# BMS_V1.net
KiCad netlist of a schematic drawn in Altium Designer
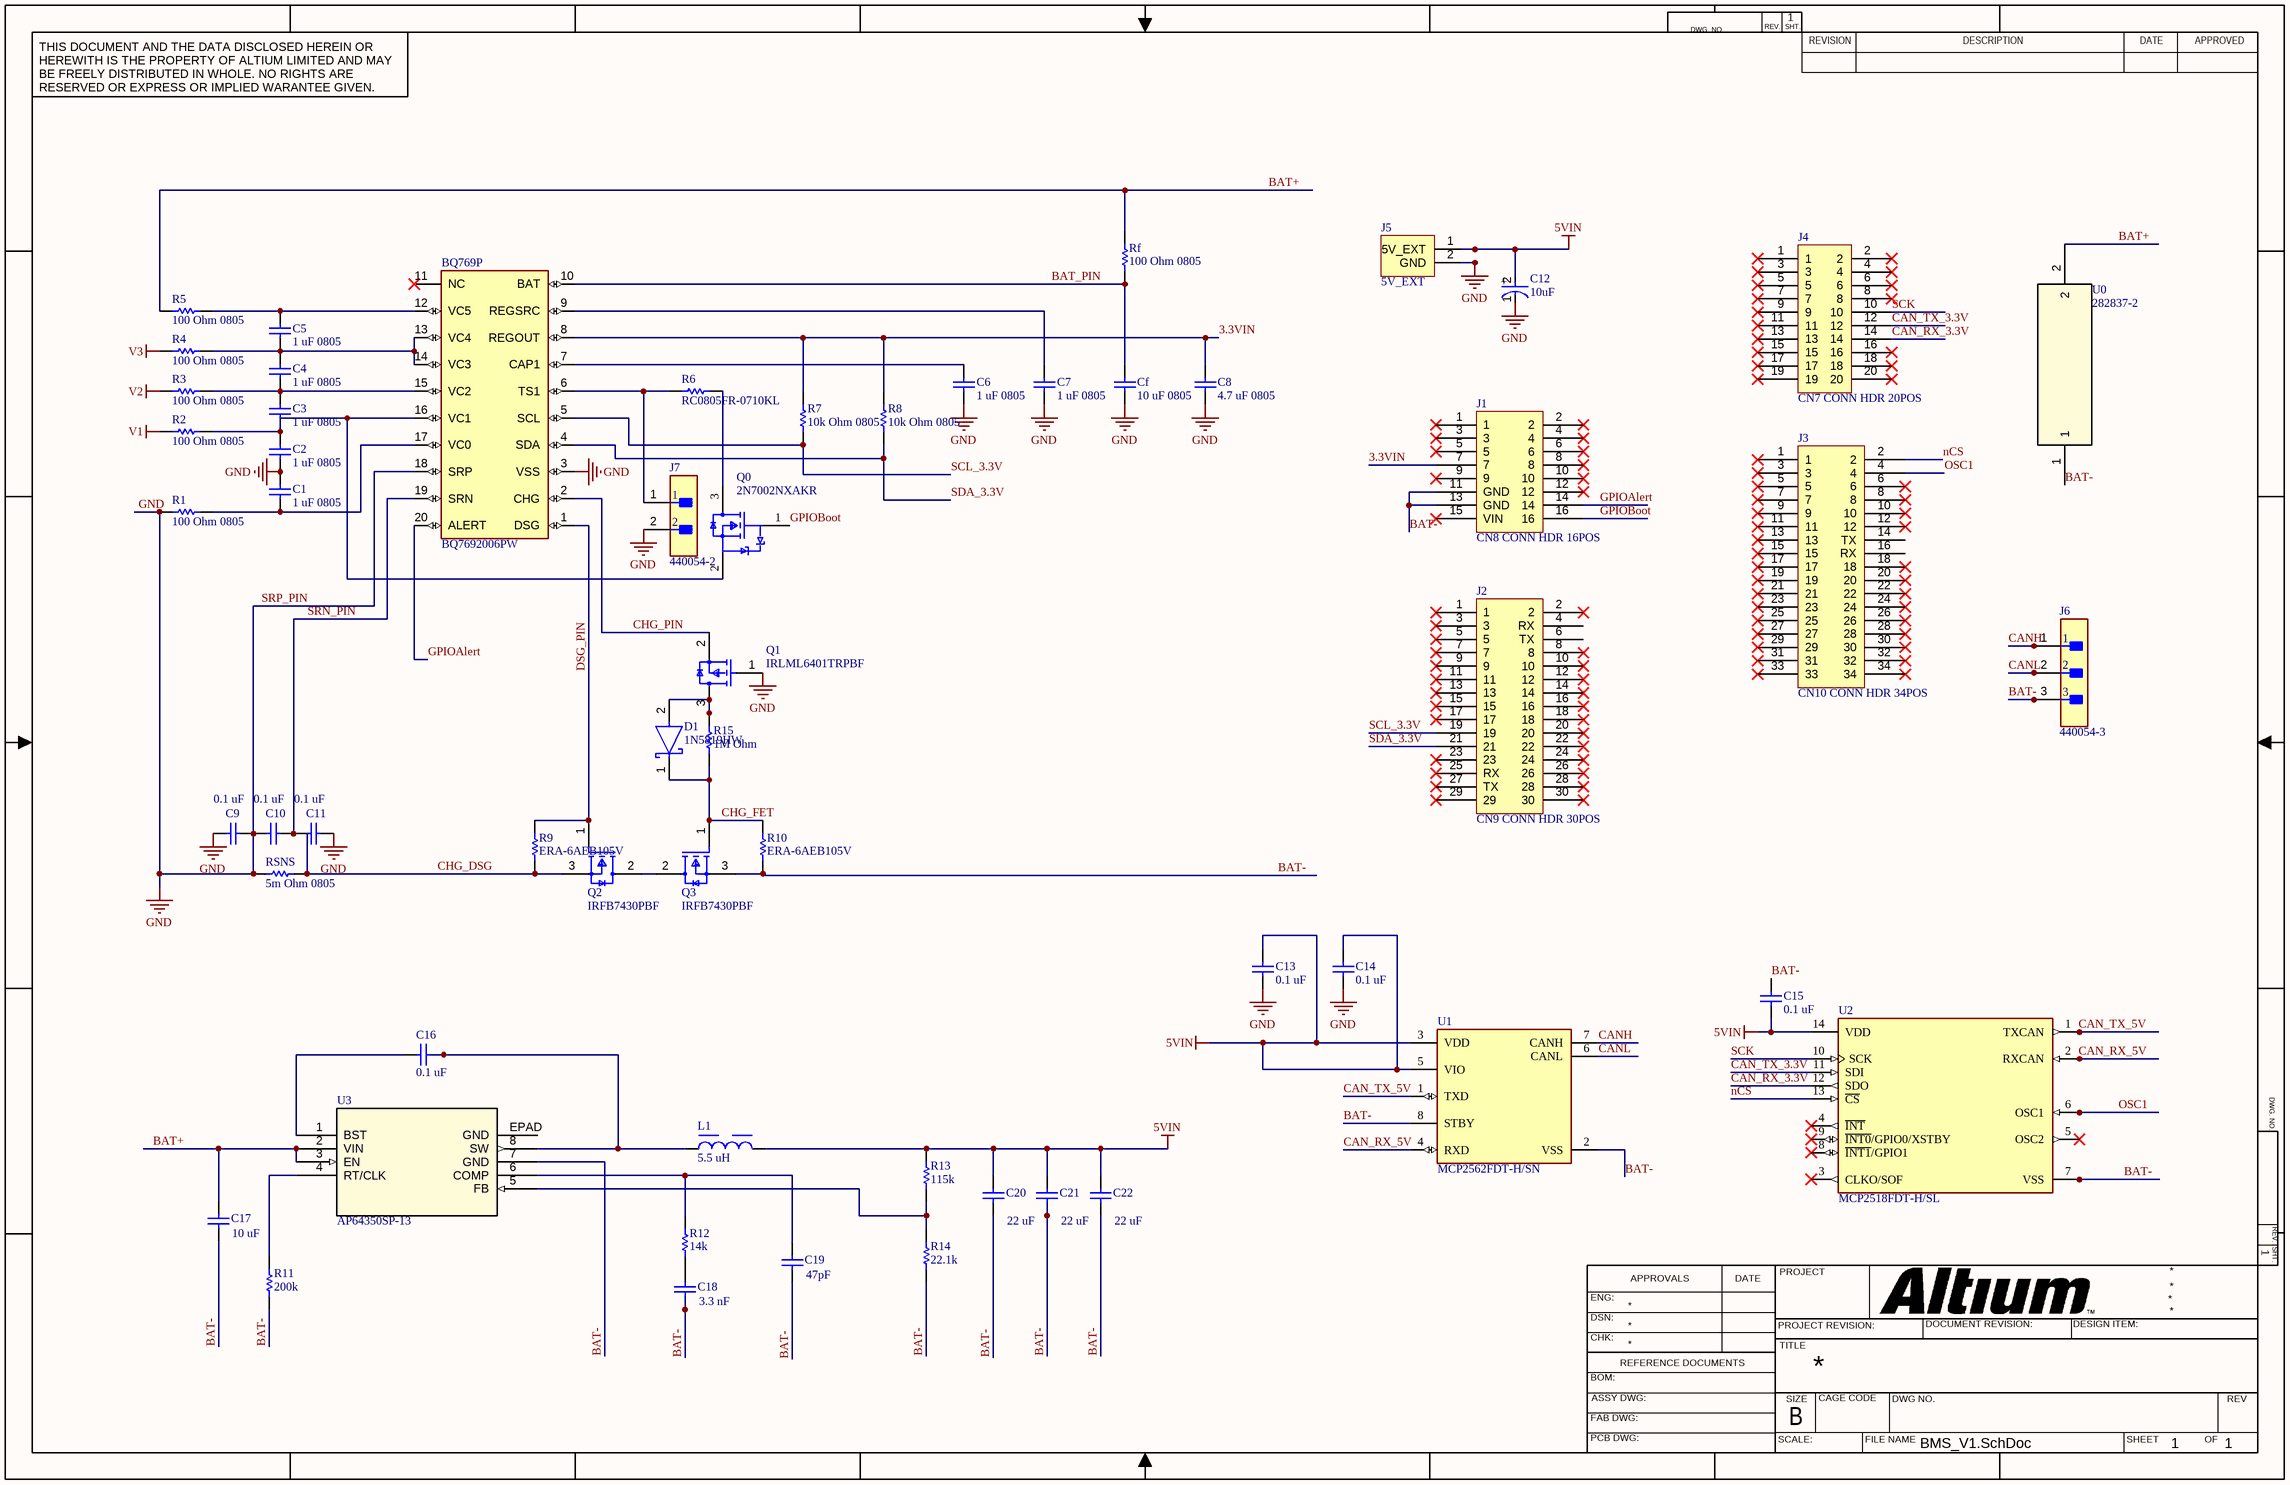
[diagram p0: BMS_V1.SchDoc]

(export (version "E")
  (design (tool "Eeschema 10.0.6"))
  (components
    (comp (ref "BQ769P")
      (value "BQ7692006PW")
      (footprint "BQ7692006PW")
      (description "3 to 5-Series Cell Li-Ion and Li-Phosphate Battery Monitor (bq76940 Family)")
      (fields (field (name "MF") "Texas Instruments"))
      (libsource (lib "Mars Colony") (part "BQ7692006PW"))
    )
    (comp (ref "C1")
      (value "1 uF 0805")
      (footprint "CAPC2013X140X50LL20T25")
      (fields (field (name "PART NUMBER") "C0805C105K3RACTU") (field (name "MANUFACTURER") "Kemet"))
      (libsource (lib "Altium Content Vault") (part "CAP"))
    )
    (comp (ref "C2")
      (value "1 uF 0805")
      (footprint "CAPC2013X140X50LL20T25")
      (fields (field (name "PART NUMBER") "C0805C105K3RACTU") (field (name "MANUFACTURER") "Kemet"))
      (libsource (lib "Altium Content Vault") (part "CAP"))
    )
    (comp (ref "C3")
      (value "1 uF 0805")
      (footprint "CAPC2013X140X50LL20T25")
      (fields (field (name "PART NUMBER") "C0805C105K3RACTU") (field (name "MANUFACTURER") "Kemet"))
      (libsource (lib "Altium Content Vault") (part "CAP"))
    )
    (comp (ref "C4")
      (value "1 uF 0805")
      (footprint "CAPC2013X140X50LL20T25")
      (fields (field (name "PART NUMBER") "C0805C105K3RACTU") (field (name "MANUFACTURER") "Kemet"))
      (libsource (lib "Altium Content Vault") (part "CAP"))
    )
    (comp (ref "C5")
      (value "1 uF 0805")
      (footprint "CAPC2013X140X50LL20T25")
      (fields (field (name "PART NUMBER") "C0805C105K3RACTU") (field (name "MANUFACTURER") "Kemet"))
      (libsource (lib "Altium Content Vault") (part "CAP"))
    )
    (comp (ref "C6")
      (value "1 uF 0805")
      (footprint "CAPC2013X140X50LL20T25")
      (fields (field (name "PART NUMBER") "C0805C105K3RACTU") (field (name "MANUFACTURER") "Kemet"))
      (libsource (lib "Altium Content Vault") (part "CAP"))
    )
    (comp (ref "C7")
      (value "1 uF 0805")
      (footprint "CAPC2013X140X50LL20T25")
      (fields (field (name "PART NUMBER") "C0805C105K3RACTU") (field (name "MANUFACTURER") "Kemet"))
      (libsource (lib "Altium Content Vault") (part "CAP"))
    )
    (comp (ref "C8")
      (value "4.7 uF 0805")
      (footprint "CAPC2013X140X50LL20T25")
      (fields (field (name "PART NUMBER") "C0805C105K3RACTU") (field (name "MANUFACTURER") "Kemet"))
      (libsource (lib "Altium Content Vault") (part "CAP"))
    )
    (comp (ref "C9")
      (value "0.1 uF")
      (footprint "CAPC2013X140X50LL20T25")
      (fields (field (name "PART NUMBER") "C0805C105K3RACTU") (field (name "MANUFACTURER") "Kemet"))
      (libsource (lib "Altium Content Vault") (part "CAP"))
    )
    (comp (ref "C10")
      (value "0.1 uF")
      (footprint "CAPC2013X140X50LL20T25")
      (fields (field (name "PART NUMBER") "C0805C105K3RACTU") (field (name "MANUFACTURER") "Kemet"))
      (libsource (lib "Altium Content Vault") (part "CAP"))
    )
    (comp (ref "C11")
      (value "0.1 uF")
      (footprint "CAPC2013X140X50LL20T25")
      (fields (field (name "PART NUMBER") "C0805C105K3RACTU") (field (name "MANUFACTURER") "Kemet"))
      (libsource (lib "Altium Content Vault") (part "CAP"))
    )
    (comp (ref "C12")
      (value "10uF")
      (footprint "FP-FKC-MFG")
      (description "CAP ALUM 10UF 20% 50V SMD")
      (fields (field (name "TOLERANCE") "20%") (field (name "VOLTAGE") "50V"))
      (libsource (lib "Altium Content Vault") (part "a00bbbee19879c290e62620ae7e47b1"))
    )
    (comp (ref "C13")
      (value "0.1 uF")
      (footprint "CAPC2013X135X45NL10T25")
      (description "Chip Capacitor, 4.7 uF, +/- 10%, 16 V, -55 to 85 degC, 0805 (2012 Metric), RoHS, Tape and Reel")
      (fields (field (name "TOLERANCE") "10%") (field (name "PARTNUMBER") "GRM21BR61C475KA88L"))
      (libsource (lib "Altium Content Vault") (part "CAP-NP-2"))
    )
    (comp (ref "C14")
      (value "0.1 uF")
      (footprint "CAPC2013X135X45NL10T25")
      (description "Chip Capacitor, 4.7 uF, +/- 10%, 16 V, -55 to 85 degC, 0805 (2012 Metric), RoHS, Tape and Reel")
      (fields (field (name "TOLERANCE") "10%") (field (name "PARTNUMBER") "GRM21BR61C475KA88L"))
      (libsource (lib "Altium Content Vault") (part "CAP-NP-2"))
    )
    (comp (ref "C15")
      (value "0.1 uF")
      (footprint "CAPC2013X135X45NL10T25")
      (description "Chip Capacitor, 4.7 uF, +/- 10%, 16 V, -55 to 85 degC, 0805 (2012 Metric), RoHS, Tape and Reel")
      (fields (field (name "TOLERANCE") "10%") (field (name "PARTNUMBER") "GRM21BR61C475KA88L"))
      (libsource (lib "Altium Content Vault") (part "CAP-NP-2"))
    )
    (comp (ref "C16")
      (value "0.1 uF")
      (footprint "CAPC2013X135X45NL10T25")
      (description "Chip Capacitor, 4.7 uF, +/- 10%, 16 V, -55 to 85 degC, 0805 (2012 Metric), RoHS, Tape and Reel")
      (fields (field (name "TOLERANCE") "10%") (field (name "PARTNUMBER") "GRM21BR61C475KA88L"))
      (libsource (lib "Altium Content Vault") (part "CAP-NP-2"))
    )
    (comp (ref "C17")
      (value "10 uF")
      (footprint "CAPC2013X135X45NL10T25")
      (description "Chip Capacitor, 4.7 uF, +/- 10%, 16 V, -55 to 85 degC, 0805 (2012 Metric), RoHS, Tape and Reel")
      (fields (field (name "TOLERANCE") "10%") (field (name "PARTNUMBER") "GRM21BR61C475KA88L"))
      (libsource (lib "Altium Content Vault") (part "CAP-NP-2"))
    )
    (comp (ref "C18")
      (value "3.3 nF")
      (footprint "CAPC2013X135X45NL10T25")
      (description "Chip Capacitor, 4.7 uF, +/- 10%, 16 V, -55 to 85 degC, 0805 (2012 Metric), RoHS, Tape and Reel")
      (fields (field (name "TOLERANCE") "10%") (field (name "PARTNUMBER") "GRM21BR61C475KA88L"))
      (libsource (lib "Altium Content Vault") (part "CAP-NP-2"))
    )
    (comp (ref "C19")
      (value "47pF")
      (footprint "CAPC2013X135X45NL10T25")
      (description "Chip Capacitor, 4.7 uF, +/- 10%, 16 V, -55 to 85 degC, 0805 (2012 Metric), RoHS, Tape and Reel")
      (fields (field (name "TOLERANCE") "10%") (field (name "PARTNUMBER") "GRM21BR61C475KA88L"))
      (libsource (lib "Altium Content Vault") (part "CAP-NP-2"))
    )
    (comp (ref "C20")
      (value "22 uF")
      (footprint "CAPC2013X135X45NL10T25")
      (description "Chip Capacitor, 4.7 uF, +/- 10%, 16 V, -55 to 85 degC, 0805 (2012 Metric), RoHS, Tape and Reel")
      (fields (field (name "TOLERANCE") "10%") (field (name "PARTNUMBER") "GRM21BR61C475KA88L"))
      (libsource (lib "Altium Content Vault") (part "CAP-NP-2"))
    )
    (comp (ref "C21")
      (value "22 uF")
      (footprint "CAPC2013X135X45NL10T25")
      (description "Chip Capacitor, 4.7 uF, +/- 10%, 16 V, -55 to 85 degC, 0805 (2012 Metric), RoHS, Tape and Reel")
      (fields (field (name "TOLERANCE") "10%") (field (name "PARTNUMBER") "GRM21BR61C475KA88L"))
      (libsource (lib "Altium Content Vault") (part "CAP-NP-2"))
    )
    (comp (ref "C22")
      (value "22 uF")
      (footprint "CAPC2013X135X45NL10T25")
      (description "Chip Capacitor, 4.7 uF, +/- 10%, 16 V, -55 to 85 degC, 0805 (2012 Metric), RoHS, Tape and Reel")
      (fields (field (name "TOLERANCE") "10%") (field (name "PARTNUMBER") "GRM21BR61C475KA88L"))
      (libsource (lib "Altium Content Vault") (part "CAP-NP-2"))
    )
    (comp (ref "Cf")
      (value "10 uF 0805")
      (footprint "CAPC2013X140X50LL20T25")
      (fields (field (name "PART NUMBER") "C0805C105K3RACTU") (field (name "MANUFACTURER") "Kemet"))
      (libsource (lib "Altium Content Vault") (part "CAP"))
    )
    (comp (ref "D1")
      (value "1N5819HW")
      (footprint "FP-SOD123-IPC_A")
      (description "DIODE SCHOTTKY 40V 1A SOD123")
      (libsource (lib "Altium Content Vault") (part "1d6ec82d83fb6aee721767c19dac4b9"))
    )
    (comp (ref "J1")
      (value "CN8 CONN HDR 16POS")
      (footprint "CN8_8X2_PADS")
      (description "CN8 CONN HDR 16POS 0.1 STACK")
      (libsource (lib "Mars Colony") (part "CN8 CONN HDR 16POS"))
    )
    (comp (ref "J2")
      (value "CN9 CONN HDR 30POS")
      (footprint "CN9_15X2_PADS")
      (description "CN9 CONN HDR 30 POS  0.1 STACK")
      (libsource (lib "Mars Colony") (part "CN9 CONN HDR 30POS"))
    )
    (comp (ref "J3")
      (value "CN10 CONN HDR 34POS")
      (footprint "CN10_17X2_PADS")
      (description "CN10 CONN HDR 34 POS  0.1 STACK")
      (libsource (lib "Mars Colony") (part "CN10 CONN HDR 34POS"))
    )
    (comp (ref "J4")
      (value "CN7 CONN HDR 20POS")
      (footprint "CN7_10X2_PADS")
      (description "CN7 CONN HDR 20 POS  0.1 STACK")
      (libsource (lib "Mars Colony") (part "CN7 CONN HDR 20POS"))
    )
    (comp (ref "J5") (value "5V_EXT") (footprint "5V_EXT") (libsource (lib "Mars Colony") (part "5V_EXT")))
    (comp (ref "J6")
      (value "440054-3")
      (footprint "FP-440054-3-MFG")
      (description "CONN HEADER VERT 3POS 2MM")
      (fields
        (field (name "OCTOPART") "https://octopart.com/440054-3-te+connectivity-40394845")
        (field (name "MANUFACTURER") "TE Connectivity")
      )
      (libsource (lib "Altium Content Vault") (part "0d3f023dd272f625e17a2be33dea85f"))
    )
    (comp (ref "J7")
      (value "440054-2")
      (footprint "FP-440054-2-MFG")
      (description "CONN HEADER VERT 2POS 2MM")
      (fields
        (field (name "MANUFACTURER") "TE Connectivity")
        (field (name "OCTOPART") "https://octopart.com/440054-2-te+connectivity-40237927")
      )
      (libsource (lib "Altium Content Vault") (part "3bc925449376181038e59eaffc5286c"))
    )
    (comp (ref "L1")
      (value "5.5 uH")
      (footprint "WE-HCI_1050")
      (fields (field (name "TOLERANCE") "20%"))
      (libsource (lib "Altium Content Vault") (part "Inductor - 3"))
    )
    (comp (ref "Q0")
      (value "2N7002NXAKR")
      (footprint "FP-SOT23-IPC_B")
      (description "2N7002NXAK/SOT23/TO-236AB")
      (libsource (lib "Altium Content Vault") (part "bf18956dcdab3ff4da62eb44f668dfe"))
    )
    (comp (ref "Q1")
      (value "IRLML6401TRPBF")
      (footprint "FP-SOT23-MFG")
      (description "MOSFET P-CH 12V 4.3A SOT-23")
      (fields
        (field (name "MANUFACTURER") "Infineon")
        (field (name "OCTOPART") "https://octopart.com/irlml6401trpbf-infineon-65874987")
      )
      (libsource (lib "Altium Content Vault") (part "28bfa747e7c25bfdd37193474a7f289"))
    )
    (comp (ref "Q2")
      (value "IRFB7430PBF")
      (footprint "FP-PG-TO220-3-MFG")
      (description "MOSFET N CH 40V 195A TO220")
      (libsource (lib "Altium Content Vault") (part "277670f45256a45703965f138927d09"))
    )
    (comp (ref "Q3")
      (value "IRFB7430PBF")
      (footprint "FP-PG-TO220-3-MFG")
      (description "MOSFET N CH 40V 195A TO220")
      (libsource (lib "Altium Content Vault") (part "277670f45256a45703965f138927d09"))
    )
    (comp (ref "R1")
      (value "100 Ohm 0805")
      (footprint "RESC2013X60X30ML20T20")
      (fields (field (name "PART NUMBER") "RK73H2ATTD1000F") (field (name "MANUFACTURER") "KOA Speer"))
      (libsource (lib "Altium Content Vault") (part "RES"))
    )
    (comp (ref "R2")
      (value "100 Ohm 0805")
      (footprint "RESC2013X60X30ML20T20")
      (fields (field (name "PART NUMBER") "RK73H2ATTD1000F") (field (name "MANUFACTURER") "KOA Speer"))
      (libsource (lib "Altium Content Vault") (part "RES"))
    )
    (comp (ref "R3")
      (value "100 Ohm 0805")
      (footprint "RESC2013X60X30ML20T20")
      (fields (field (name "PART NUMBER") "RK73H2ATTD1000F") (field (name "MANUFACTURER") "KOA Speer"))
      (libsource (lib "Altium Content Vault") (part "RES"))
    )
    (comp (ref "R4")
      (value "100 Ohm 0805")
      (footprint "RESC2013X60X30ML20T20")
      (fields (field (name "PART NUMBER") "RK73H2ATTD1000F") (field (name "MANUFACTURER") "KOA Speer"))
      (libsource (lib "Altium Content Vault") (part "RES"))
    )
    (comp (ref "R5")
      (value "100 Ohm 0805")
      (footprint "RESC2013X60X30ML20T20")
      (fields (field (name "PART NUMBER") "RK73H2ATTD1000F") (field (name "MANUFACTURER") "KOA Speer"))
      (libsource (lib "Altium Content Vault") (part "RES"))
    )
    (comp (ref "R6")
      (value "RC0805FR-0710KL")
      (footprint "RESC2013X60X35NL10T20")
      (description "Chip Resistor, 10 KOhm, +/- 1%, 0.125 W, -55 to 155 degC, 0805 (2012 Metric), RoHS, Tape and Reel")
      (fields (field (name "MANUFACTURER") "Yageo"))
      (libsource (lib "Altium Content Vault") (part "RES-2"))
    )
    (comp (ref "R7")
      (value "10k Ohm 0805")
      (footprint "RESC2013X60X30ML20T20")
      (fields (field (name "PART NUMBER") "RK73H2ATTD1000F") (field (name "MANUFACTURER") "KOA Speer"))
      (libsource (lib "Altium Content Vault") (part "RES"))
    )
    (comp (ref "R8")
      (value "10k Ohm 0805")
      (footprint "RESC2013X60X30ML20T20")
      (fields (field (name "PART NUMBER") "RK73H2ATTD1000F") (field (name "MANUFACTURER") "KOA Speer"))
      (libsource (lib "Altium Content Vault") (part "RES"))
    )
    (comp (ref "R9")
      (value "ERA-6AEB105V")
      (footprint "RESC2013X60X40LL20T25")
      (fields (field (name "MANUFACTURER") "Panasonic"))
      (libsource (lib "Altium Content Vault") (part "RES"))
    )
    (comp (ref "R10")
      (value "ERA-6AEB105V")
      (footprint "RESC2013X60X40LL20T25")
      (fields (field (name "MANUFACTURER") "Panasonic"))
      (libsource (lib "Altium Content Vault") (part "RES"))
    )
    (comp (ref "R11")
      (value "200k")
      (footprint "RESC2013X60X35ML10T20")
      (description "Chip Resistor, 1 KOhm, +/- 1%, 125 mW, -55 to 155 degC, 0805 (2012 Metric), RoHS, Tape and Reel")
      (fields (field (name "TOLERANCE") "1%") (field (name "MANUFACTURER") "Yageo"))
      (libsource (lib "Altium Content Vault") (part "RES-2"))
    )
    (comp (ref "R12")
      (value "14k")
      (footprint "RESC2013X60X35ML10T20")
      (description "Chip Resistor, 1 KOhm, +/- 1%, 125 mW, -55 to 155 degC, 0805 (2012 Metric), RoHS, Tape and Reel")
      (fields (field (name "TOLERANCE") "1%") (field (name "MANUFACTURER") "Yageo"))
      (libsource (lib "Altium Content Vault") (part "RES-2"))
    )
    (comp (ref "R13")
      (value "115k")
      (footprint "RESC2013X60X35ML10T20")
      (description "Chip Resistor, 1 KOhm, +/- 1%, 125 mW, -55 to 155 degC, 0805 (2012 Metric), RoHS, Tape and Reel")
      (fields (field (name "TOLERANCE") "1%") (field (name "MANUFACTURER") "Yageo"))
      (libsource (lib "Altium Content Vault") (part "RES-2"))
    )
    (comp (ref "R14")
      (value "22.1k")
      (footprint "RESC2013X60X35ML10T20")
      (description "Chip Resistor, 1 KOhm, +/- 1%, 125 mW, -55 to 155 degC, 0805 (2012 Metric), RoHS, Tape and Reel")
      (fields (field (name "TOLERANCE") "1%") (field (name "MANUFACTURER") "Yageo"))
      (libsource (lib "Altium Content Vault") (part "RES-2"))
    )
    (comp (ref "R15")
      (value "1M Ohm")
      (footprint "RESC2013X60X40LL20T25")
      (fields (field (name "PART NUMBER") "ERA-6AEB105V") (field (name "MANUFACTURER") "Panasonic"))
      (libsource (lib "Altium Content Vault") (part "RES"))
    )
    (comp (ref "Rf")
      (value "100 Ohm 0805")
      (footprint "RESC2013X60X30ML20T20")
      (fields (field (name "PART NUMBER") "RK73H2ATTD1000F") (field (name "MANUFACTURER") "KOA Speer"))
      (libsource (lib "Altium Content Vault") (part "RES"))
    )
    (comp (ref "RSNS")
      (value "5m Ohm 0805")
      (footprint "RESC2013X60X30ML20T20")
      (fields (field (name "PART NUMBER") "RK73H2ATTD1000F") (field (name "MANUFACTURER") "KOA Speer"))
      (libsource (lib "Altium Content Vault") (part "RES"))
    )
    (comp (ref "U0")
      (value "282837-2")
      (footprint "282837-2_TYC")
      (description "No Description Available")
      (libsource (lib "Mars Colony") (part "282837-2"))
    )
    (comp (ref "U1")
      (value "MCP2562FDT-H/SN")
      (footprint "FP-C04-057-SN-IPC_A")
      (description "IC TRANSCEIVER 1/1 8SOIC")
      (libsource (lib "Altium Content Vault") (part "d4eccbb03d796c5d2cef85367bb866b"))
    )
    (comp (ref "U2")
      (value "MCP2518FDT-H/SL")
      (footprint "FP-C04-065-SL-IPC_B")
      (description "IC CAN CONTROLLER SPI 14SOIC")
      (libsource (lib "Altium Content Vault") (part "6e4b5c1966b5a02aedfdd71ccf535af"))
    )
    (comp (ref "U3")
      (value "AP64350SP-13")
      (footprint "SO-8EP_DIO")
      (description "No Description Available")
      (libsource (lib "Mars Colony") (part "AP64350SP-13"))
    )
  )
  (nets
    (net (code "1") (name "/3.3VIN") (class "Default")
      (node (ref "BQ769P") (pin "8") (pinfunction "REGOUT_8") (pintype "bidirectional"))
      (node (ref "C8") (pin "2") (pinfunction "2_2") (pintype "passive"))
      (node (ref "J1") (pin "7") (pinfunction "7_7") (pintype "passive"))
      (node (ref "R7") (pin "2") (pinfunction "2_2") (pintype "passive"))
      (node (ref "R8") (pin "2") (pinfunction "2_2") (pintype "passive"))
    )
    (net (code "2") (name "/BAT+") (class "Default")
      (node (ref "C17") (pin "2") (pinfunction "2_2") (pintype "passive"))
      (node (ref "R5") (pin "1") (pinfunction "1_1") (pintype "passive"))
      (node (ref "Rf") (pin "2") (pinfunction "2_2") (pintype "passive"))
      (node (ref "U0") (pin "2") (pinfunction "2_2") (pintype "passive"))
      (node (ref "U3") (pin "2") (pinfunction "VIN_2") (pintype "power_in"))
      (node (ref "U3") (pin "3") (pinfunction "EN_3") (pintype "input"))
    )
    (net (code "3") (name "/BAT-") (class "Default")
      (node (ref "C15") (pin "2") (pinfunction "2_2") (pintype "passive"))
      (node (ref "C17") (pin "1") (pinfunction "1_1") (pintype "passive"))
      (node (ref "C18") (pin "1") (pinfunction "1_1") (pintype "passive"))
      (node (ref "C19") (pin "1") (pinfunction "1_1") (pintype "passive"))
      (node (ref "C20") (pin "1") (pinfunction "1_1") (pintype "passive"))
      (node (ref "C21") (pin "1") (pinfunction "1_1") (pintype "passive"))
      (node (ref "C22") (pin "1") (pinfunction "1_1") (pintype "passive"))
      (node (ref "J1") (pin "11") (pinfunction "GND_11") (pintype "passive"))
      (node (ref "J1") (pin "13") (pinfunction "GND_13") (pintype "passive"))
      (node (ref "J6") (pin "3") (pinfunction "3_3") (pintype "passive"))
      (node (ref "Q3") (pin "3") (pinfunction "S_3") (pintype "passive"))
      (node (ref "R10") (pin "1") (pinfunction "1_1") (pintype "passive"))
      (node (ref "R11") (pin "1") (pinfunction "1_1") (pintype "passive"))
      (node (ref "R14") (pin "1") (pinfunction "1_1") (pintype "passive"))
      (node (ref "U0") (pin "1") (pinfunction "1_1") (pintype "passive"))
      (node (ref "U1") (pin "2") (pinfunction "VSS_2") (pintype "power_in"))
      (node (ref "U1") (pin "8") (pinfunction "STBY_8") (pintype "passive"))
      (node (ref "U2") (pin "7") (pinfunction "VSS_7") (pintype "power_in"))
      (node (ref "U3") (pin "7") (pinfunction "GND_7") (pintype "power_in"))
    )
    (net (code "4") (name "/BAT_PIN") (class "Default")
      (node (ref "BQ769P") (pin "10") (pinfunction "BAT_10") (pintype "bidirectional"))
      (node (ref "Cf") (pin "2") (pinfunction "2_2") (pintype "passive"))
      (node (ref "Rf") (pin "1") (pinfunction "1_1") (pintype "passive"))
    )
    (net (code "5") (name "/CANH") (class "Default")
      (node (ref "J6") (pin "1") (pinfunction "1_1") (pintype "passive"))
      (node (ref "U1") (pin "7") (pinfunction "CANH_7") (pintype "passive"))
    )
    (net (code "6") (name "/CANL") (class "Default")
      (node (ref "J6") (pin "2") (pinfunction "2_2") (pintype "passive"))
      (node (ref "U1") (pin "6") (pinfunction "CANL_6") (pintype "passive"))
    )
    (net (code "7") (name "/CAN_RX_3.3V") (class "Default")
      (node (ref "J4") (pin "14") (pinfunction "14_14") (pintype "passive"))
      (node (ref "U2") (pin "12") (pinfunction "SDO_12") (pintype "output"))
    )
    (net (code "8") (name "/CAN_RX_5V") (class "Default")
      (node (ref "U1") (pin "4") (pinfunction "RXD_4") (pintype "bidirectional"))
      (node (ref "U2") (pin "2") (pinfunction "RXCAN_2") (pintype "input"))
    )
    (net (code "9") (name "/CAN_TX_3.3V") (class "Default")
      (node (ref "J4") (pin "12") (pinfunction "12_12") (pintype "passive"))
      (node (ref "U2") (pin "11") (pinfunction "SDI_11") (pintype "input"))
    )
    (net (code "10") (name "/CAN_TX_5V") (class "Default")
      (node (ref "U1") (pin "1") (pinfunction "TXD_1") (pintype "bidirectional"))
      (node (ref "U2") (pin "1") (pinfunction "TXCAN_1") (pintype "output"))
    )
    (net (code "11") (name "/CHG_DSG") (class "Default")
      (node (ref "Q2") (pin "3") (pinfunction "S_3") (pintype "passive"))
      (node (ref "R9") (pin "1") (pinfunction "1_1") (pintype "passive"))
      (node (ref "RSNS") (pin "1") (pinfunction "1_1") (pintype "passive"))
    )
    (net (code "12") (name "/CHG_FET") (class "Default")
      (node (ref "D1") (pin "1") (pinfunction "C_1") (pintype "passive"))
      (node (ref "Q3") (pin "1") (pinfunction "G_1") (pintype "passive"))
      (node (ref "R10") (pin "2") (pinfunction "2_2") (pintype "passive"))
      (node (ref "R15") (pin "1") (pinfunction "1_1") (pintype "passive"))
    )
    (net (code "13") (name "/CHG_PIN") (class "Default")
      (node (ref "BQ769P") (pin "2") (pinfunction "CHG_2") (pintype "bidirectional"))
      (node (ref "Q1") (pin "2") (pinfunction "S_2") (pintype "passive"))
    )
    (net (code "14") (name "/DSG_PIN") (class "Default")
      (node (ref "BQ769P") (pin "1") (pinfunction "DSG_1") (pintype "bidirectional"))
      (node (ref "Q2") (pin "1") (pinfunction "G_1") (pintype "passive"))
      (node (ref "R9") (pin "2") (pinfunction "2_2") (pintype "passive"))
    )
    (net (code "15") (name "/GPIOAlert") (class "Default")
      (node (ref "BQ769P") (pin "20") (pinfunction "ALERT_20") (pintype "bidirectional"))
      (node (ref "J1") (pin "14") (pinfunction "14_14") (pintype "passive"))
    )
    (net (code "16") (name "/GPIOBoot") (class "Default")
      (node (ref "J1") (pin "16") (pinfunction "16_16") (pintype "passive"))
      (node (ref "Q0") (pin "1") (pinfunction "G_1") (pintype "passive"))
    )
    (net (code "17") (name "/OSC1") (class "Default")
      (node (ref "J3") (pin "4") (pinfunction "4_4") (pintype "passive"))
      (node (ref "U2") (pin "6") (pinfunction "OSC1_6") (pintype "input"))
    )
    (net (code "18") (name "/SCK") (class "Default")
      (node (ref "J4") (pin "10") (pinfunction "10_10") (pintype "passive"))
      (node (ref "U2") (pin "10") (pinfunction "SCK_10") (pintype "input"))
    )
    (net (code "19") (name "/SCL_3.3V") (class "Default")
      (node (ref "BQ769P") (pin "5") (pinfunction "SCL_5") (pintype "bidirectional"))
      (node (ref "J2") (pin "19") (pinfunction "19_19") (pintype "passive"))
      (node (ref "R7") (pin "1") (pinfunction "1_1") (pintype "passive"))
    )
    (net (code "20") (name "/SDA_3.3V") (class "Default")
      (node (ref "BQ769P") (pin "4") (pinfunction "SDA_4") (pintype "bidirectional"))
      (node (ref "J2") (pin "21") (pinfunction "21_21") (pintype "passive"))
      (node (ref "R8") (pin "1") (pinfunction "1_1") (pintype "passive"))
    )
    (net (code "21") (name "/SRN_PIN") (class "Default")
      (node (ref "BQ769P") (pin "19") (pinfunction "SRN_19") (pintype "bidirectional"))
      (node (ref "C10") (pin "1") (pinfunction "1_1") (pintype "passive"))
      (node (ref "C11") (pin "2") (pinfunction "2_2") (pintype "passive"))
    )
    (net (code "22") (name "/nCS") (class "Default")
      (node (ref "J3") (pin "2") (pinfunction "2_2") (pintype "passive"))
      (node (ref "U2") (pin "13") (pinfunction "~{CS}_13") (pintype "input"))
    )
    (net (code "23") (name "5VIN") (class "Default")
      (node (ref "C12") (pin "2") (pinfunction "A_2") (pintype "passive"))
      (node (ref "C13") (pin "2") (pinfunction "2_2") (pintype "passive"))
      (node (ref "C14") (pin "2") (pinfunction "2_2") (pintype "passive"))
      (node (ref "C15") (pin "1") (pinfunction "1_1") (pintype "passive"))
      (node (ref "C20") (pin "2") (pinfunction "2_2") (pintype "passive"))
      (node (ref "C21") (pin "2") (pinfunction "2_2") (pintype "passive"))
      (node (ref "C22") (pin "2") (pinfunction "2_2") (pintype "passive"))
      (node (ref "J5") (pin "1") (pinfunction "5V_EXT_1") (pintype "passive"))
      (node (ref "L1") (pin "2") (pinfunction "2_2") (pintype "passive"))
      (node (ref "R13") (pin "2") (pinfunction "2_2") (pintype "passive"))
      (node (ref "U1") (pin "3") (pinfunction "VDD_3") (pintype "power_in"))
      (node (ref "U1") (pin "5") (pinfunction "VIO_5") (pintype "power_in"))
      (node (ref "U2") (pin "14") (pinfunction "VDD_14") (pintype "power_in"))
    )
    (net (code "24") (name "GND") (class "Default")
      (node (ref "BQ769P") (pin "18") (pinfunction "SRP_18") (pintype "bidirectional"))
      (node (ref "BQ769P") (pin "3") (pinfunction "VSS_3") (pintype "bidirectional"))
      (node (ref "C1") (pin "2") (pinfunction "2_2") (pintype "passive"))
      (node (ref "C10") (pin "2") (pinfunction "2_2") (pintype "passive"))
      (node (ref "C11") (pin "1") (pinfunction "1_1") (pintype "passive"))
      (node (ref "C12") (pin "1") (pinfunction "C_1") (pintype "passive"))
      (node (ref "C13") (pin "1") (pinfunction "1_1") (pintype "passive"))
      (node (ref "C14") (pin "1") (pinfunction "1_1") (pintype "passive"))
      (node (ref "C2") (pin "1") (pinfunction "1_1") (pintype "passive"))
      (node (ref "C6") (pin "1") (pinfunction "1_1") (pintype "passive"))
      (node (ref "C7") (pin "1") (pinfunction "1_1") (pintype "passive"))
      (node (ref "C8") (pin "1") (pinfunction "1_1") (pintype "passive"))
      (node (ref "C9") (pin "1") (pinfunction "1_1") (pintype "passive"))
      (node (ref "C9") (pin "2") (pinfunction "2_2") (pintype "passive"))
      (node (ref "Cf") (pin "1") (pinfunction "1_1") (pintype "passive"))
      (node (ref "J5") (pin "2") (pinfunction "GND_2") (pintype "passive"))
      (node (ref "J7") (pin "2") (pinfunction "2_2") (pintype "passive"))
      (node (ref "Q1") (pin "1") (pinfunction "G_1") (pintype "passive"))
      (node (ref "R1") (pin "1") (pinfunction "1_1") (pintype "passive"))
      (node (ref "RSNS") (pin "2") (pinfunction "2_2") (pintype "passive"))
    )
    (net (code "25") (name "Net-(BQ769P-CAP1)") (class "Default")
      (node (ref "BQ769P") (pin "7") (pinfunction "CAP1_7") (pintype "bidirectional"))
      (node (ref "C6") (pin "2") (pinfunction "2_2") (pintype "passive"))
    )
    (net (code "26") (name "Net-(BQ769P-REGSRC)") (class "Default")
      (node (ref "BQ769P") (pin "9") (pinfunction "REGSRC_9") (pintype "bidirectional"))
      (node (ref "C7") (pin "2") (pinfunction "2_2") (pintype "passive"))
    )
    (net (code "27") (name "Net-(BQ769P-TS1)") (class "Default")
      (node (ref "BQ769P") (pin "6") (pinfunction "TS1_6") (pintype "bidirectional"))
      (node (ref "J7") (pin "1") (pinfunction "1_1") (pintype "passive"))
      (node (ref "R6") (pin "1") (pinfunction "1_1") (pintype "passive"))
    )
    (net (code "28") (name "Net-(BQ769P-VC0)") (class "Default")
      (node (ref "BQ769P") (pin "17") (pinfunction "VC0_17") (pintype "bidirectional"))
      (node (ref "C1") (pin "1") (pinfunction "1_1") (pintype "passive"))
      (node (ref "R1") (pin "2") (pinfunction "2_2") (pintype "passive"))
    )
    (net (code "29") (name "Net-(BQ769P-VC1)") (class "Default")
      (node (ref "BQ769P") (pin "16") (pinfunction "VC1_16") (pintype "bidirectional"))
      (node (ref "C2") (pin "2") (pinfunction "2_2") (pintype "passive"))
      (node (ref "C3") (pin "1") (pinfunction "1_1") (pintype "passive"))
      (node (ref "Q0") (pin "2") (pinfunction "S_2") (pintype "passive"))
      (node (ref "R2") (pin "2") (pinfunction "2_2") (pintype "passive"))
    )
    (net (code "30") (name "Net-(BQ769P-VC2)") (class "Default")
      (node (ref "BQ769P") (pin "15") (pinfunction "VC2_15") (pintype "bidirectional"))
      (node (ref "C3") (pin "2") (pinfunction "2_2") (pintype "passive"))
      (node (ref "C4") (pin "1") (pinfunction "1_1") (pintype "passive"))
      (node (ref "R3") (pin "2") (pinfunction "2_2") (pintype "passive"))
    )
    (net (code "31") (name "Net-(BQ769P-VC3)") (class "Default")
      (node (ref "BQ769P") (pin "13") (pinfunction "VC4_13") (pintype "bidirectional"))
      (node (ref "BQ769P") (pin "14") (pinfunction "VC3_14") (pintype "bidirectional"))
      (node (ref "C4") (pin "2") (pinfunction "2_2") (pintype "passive"))
      (node (ref "C5") (pin "1") (pinfunction "1_1") (pintype "passive"))
      (node (ref "R4") (pin "2") (pinfunction "2_2") (pintype "passive"))
    )
    (net (code "32") (name "Net-(BQ769P-VC5)") (class "Default")
      (node (ref "BQ769P") (pin "12") (pinfunction "VC5_12") (pintype "bidirectional"))
      (node (ref "C5") (pin "2") (pinfunction "2_2") (pintype "passive"))
      (node (ref "R5") (pin "2") (pinfunction "2_2") (pintype "passive"))
    )
    (net (code "33") (name "Net-(C18-Pad2)") (class "Default")
      (node (ref "C18") (pin "2") (pinfunction "2_2") (pintype "passive"))
      (node (ref "R12") (pin "1") (pinfunction "1_1") (pintype "passive"))
    )
    (net (code "34") (name "Net-(D1-A)") (class "Default")
      (node (ref "D1") (pin "2") (pinfunction "A_2") (pintype "passive"))
      (node (ref "Q1") (pin "3") (pinfunction "D_3") (pintype "passive"))
      (node (ref "R15") (pin "2") (pinfunction "2_2") (pintype "passive"))
    )
    (net (code "35") (name "Net-(Q0-D)") (class "Default")
      (node (ref "Q0") (pin "3") (pinfunction "D_3") (pintype "passive"))
      (node (ref "R6") (pin "2") (pinfunction "2_2") (pintype "passive"))
    )
    (net (code "36") (name "Net-(Q2-D)") (class "Default")
      (node (ref "Q2") (pin "2") (pinfunction "D_2") (pintype "passive"))
      (node (ref "Q3") (pin "2") (pinfunction "D_2") (pintype "passive"))
    )
    (net (code "37") (name "Net-(U3-BST)") (class "Default")
      (node (ref "C16") (pin "2") (pinfunction "2_2") (pintype "passive"))
      (node (ref "U3") (pin "1") (pinfunction "BST_1") (pintype "power_in"))
    )
    (net (code "38") (name "Net-(U3-COMP)") (class "Default")
      (node (ref "C19") (pin "2") (pinfunction "2_2") (pintype "passive"))
      (node (ref "R12") (pin "2") (pinfunction "2_2") (pintype "passive"))
      (node (ref "U3") (pin "6") (pinfunction "COMP_6") (pintype "passive"))
    )
    (net (code "39") (name "Net-(U3-FB)") (class "Default")
      (node (ref "R13") (pin "1") (pinfunction "1_1") (pintype "passive"))
      (node (ref "R14") (pin "2") (pinfunction "2_2") (pintype "passive"))
      (node (ref "U3") (pin "5") (pinfunction "FB_5") (pintype "input"))
    )
    (net (code "40") (name "Net-(U3-RT{slash}CLK)") (class "Default")
      (node (ref "R11") (pin "2") (pinfunction "2_2") (pintype "passive"))
      (node (ref "U3") (pin "4") (pinfunction "RT/CLK_4") (pintype "passive"))
    )
    (net (code "41") (name "Net-(U3-SW)") (class "Default")
      (node (ref "C16") (pin "1") (pinfunction "1_1") (pintype "passive"))
      (node (ref "L1") (pin "1") (pinfunction "1_1") (pintype "passive"))
      (node (ref "U3") (pin "8") (pinfunction "SW_8") (pintype "output"))
    )
    (net (code "42") (name "V1") (class "Default")
      (node (ref "R2") (pin "1") (pinfunction "1_1") (pintype "passive"))
    )
    (net (code "43") (name "V2") (class "Default")
      (node (ref "R3") (pin "1") (pinfunction "1_1") (pintype "passive"))
    )
    (net (code "44") (name "V3") (class "Default")
      (node (ref "R4") (pin "1") (pinfunction "1_1") (pintype "passive"))
    )
    (net (code "45") (name "unconnected-(BQ769P-NC-Pad11)") (class "Default")
      (node (ref "BQ769P") (pin "11") (pinfunction "NC_11") (pintype "passive+no_connect"))
    )
    (net (code "46") (name "unconnected-(J1-Pad1)") (class "Default")
      (node (ref "J1") (pin "1") (pinfunction "1_1") (pintype "passive+no_connect"))
    )
    (net (code "47") (name "unconnected-(J1-Pad2)") (class "Default")
      (node (ref "J1") (pin "2") (pinfunction "2_2") (pintype "passive+no_connect"))
    )
    (net (code "48") (name "unconnected-(J1-Pad3)") (class "Default")
      (node (ref "J1") (pin "3") (pinfunction "3_3") (pintype "passive+no_connect"))
    )
    (net (code "49") (name "unconnected-(J1-Pad4)") (class "Default")
      (node (ref "J1") (pin "4") (pinfunction "4_4") (pintype "passive+no_connect"))
    )
    (net (code "50") (name "unconnected-(J1-Pad5)") (class "Default")
      (node (ref "J1") (pin "5") (pinfunction "5_5") (pintype "passive+no_connect"))
    )
    (net (code "51") (name "unconnected-(J1-Pad6)") (class "Default")
      (node (ref "J1") (pin "6") (pinfunction "6_6") (pintype "passive+no_connect"))
    )
    (net (code "52") (name "unconnected-(J1-Pad8)") (class "Default")
      (node (ref "J1") (pin "8") (pinfunction "8_8") (pintype "passive+no_connect"))
    )
    (net (code "53") (name "unconnected-(J1-Pad9)") (class "Default")
      (node (ref "J1") (pin "9") (pinfunction "9_9") (pintype "passive+no_connect"))
    )
    (net (code "54") (name "unconnected-(J1-Pad10)") (class "Default")
      (node (ref "J1") (pin "10") (pinfunction "10_10") (pintype "passive+no_connect"))
    )
    (net (code "55") (name "unconnected-(J1-Pad12)") (class "Default")
      (node (ref "J1") (pin "12") (pinfunction "12_12") (pintype "passive+no_connect"))
    )
    (net (code "56") (name "unconnected-(J1-VIN-Pad15)") (class "Default")
      (node (ref "J1") (pin "15") (pinfunction "VIN_15") (pintype "passive+no_connect"))
    )
    (net (code "57") (name "unconnected-(J2-Pad1)") (class "Default")
      (node (ref "J2") (pin "1") (pinfunction "1_1") (pintype "passive+no_connect"))
    )
    (net (code "58") (name "unconnected-(J2-Pad2)") (class "Default")
      (node (ref "J2") (pin "2") (pinfunction "2_2") (pintype "passive+no_connect"))
    )
    (net (code "59") (name "unconnected-(J2-Pad3)") (class "Default")
      (node (ref "J2") (pin "3") (pinfunction "3_3") (pintype "passive+no_connect"))
    )
    (net (code "60") (name "unconnected-(J2-Pad5)") (class "Default")
      (node (ref "J2") (pin "5") (pinfunction "5_5") (pintype "passive+no_connect"))
    )
    (net (code "61") (name "unconnected-(J2-Pad7)") (class "Default")
      (node (ref "J2") (pin "7") (pinfunction "7_7") (pintype "passive+no_connect"))
    )
    (net (code "62") (name "unconnected-(J2-Pad8)") (class "Default")
      (node (ref "J2") (pin "8") (pinfunction "8_8") (pintype "passive+no_connect"))
    )
    (net (code "63") (name "unconnected-(J2-Pad9)") (class "Default")
      (node (ref "J2") (pin "9") (pinfunction "9_9") (pintype "passive+no_connect"))
    )
    (net (code "64") (name "unconnected-(J2-Pad10)") (class "Default")
      (node (ref "J2") (pin "10") (pinfunction "10_10") (pintype "passive+no_connect"))
    )
    (net (code "65") (name "unconnected-(J2-Pad11)") (class "Default")
      (node (ref "J2") (pin "11") (pinfunction "11_11") (pintype "passive+no_connect"))
    )
    (net (code "66") (name "unconnected-(J2-Pad12)") (class "Default")
      (node (ref "J2") (pin "12") (pinfunction "12_12") (pintype "passive+no_connect"))
    )
    (net (code "67") (name "unconnected-(J2-Pad13)") (class "Default")
      (node (ref "J2") (pin "13") (pinfunction "13_13") (pintype "passive+no_connect"))
    )
    (net (code "68") (name "unconnected-(J2-Pad14)") (class "Default")
      (node (ref "J2") (pin "14") (pinfunction "14_14") (pintype "passive+no_connect"))
    )
    (net (code "69") (name "unconnected-(J2-Pad15)") (class "Default")
      (node (ref "J2") (pin "15") (pinfunction "15_15") (pintype "passive+no_connect"))
    )
    (net (code "70") (name "unconnected-(J2-Pad16)") (class "Default")
      (node (ref "J2") (pin "16") (pinfunction "16_16") (pintype "passive+no_connect"))
    )
    (net (code "71") (name "unconnected-(J2-Pad17)") (class "Default")
      (node (ref "J2") (pin "17") (pinfunction "17_17") (pintype "passive+no_connect"))
    )
    (net (code "72") (name "unconnected-(J2-Pad18)") (class "Default")
      (node (ref "J2") (pin "18") (pinfunction "18_18") (pintype "passive+no_connect"))
    )
    (net (code "73") (name "unconnected-(J2-Pad20)") (class "Default")
      (node (ref "J2") (pin "20") (pinfunction "20_20") (pintype "passive+no_connect"))
    )
    (net (code "74") (name "unconnected-(J2-Pad22)") (class "Default")
      (node (ref "J2") (pin "22") (pinfunction "22_22") (pintype "passive+no_connect"))
    )
    (net (code "75") (name "unconnected-(J2-Pad23)") (class "Default")
      (node (ref "J2") (pin "23") (pinfunction "23_23") (pintype "passive+no_connect"))
    )
    (net (code "76") (name "unconnected-(J2-Pad24)") (class "Default")
      (node (ref "J2") (pin "24") (pinfunction "24_24") (pintype "passive+no_connect"))
    )
    (net (code "77") (name "unconnected-(J2-Pad26)") (class "Default")
      (node (ref "J2") (pin "26") (pinfunction "26_26") (pintype "passive+no_connect"))
    )
    (net (code "78") (name "unconnected-(J2-Pad28)") (class "Default")
      (node (ref "J2") (pin "28") (pinfunction "28_28") (pintype "passive+no_connect"))
    )
    (net (code "79") (name "unconnected-(J2-Pad29)") (class "Default")
      (node (ref "J2") (pin "29") (pinfunction "29_29") (pintype "passive+no_connect"))
    )
    (net (code "80") (name "unconnected-(J2-Pad30)") (class "Default")
      (node (ref "J2") (pin "30") (pinfunction "30_30") (pintype "passive+no_connect"))
    )
    (net (code "81") (name "unconnected-(J2-RX-Pad4)") (class "Default")
      (node (ref "J2") (pin "4") (pinfunction "RX_4") (pintype "passive"))
    )
    (net (code "82") (name "unconnected-(J2-RX-Pad25)") (class "Default")
      (node (ref "J2") (pin "25") (pinfunction "RX_25") (pintype "passive+no_connect"))
    )
    (net (code "83") (name "unconnected-(J2-TX-Pad6)") (class "Default")
      (node (ref "J2") (pin "6") (pinfunction "TX_6") (pintype "passive"))
    )
    (net (code "84") (name "unconnected-(J2-TX-Pad27)") (class "Default")
      (node (ref "J2") (pin "27") (pinfunction "TX_27") (pintype "passive+no_connect"))
    )
    (net (code "85") (name "unconnected-(J3-Pad1)") (class "Default")
      (node (ref "J3") (pin "1") (pinfunction "1_1") (pintype "passive+no_connect"))
    )
    (net (code "86") (name "unconnected-(J3-Pad3)") (class "Default")
      (node (ref "J3") (pin "3") (pinfunction "3_3") (pintype "passive+no_connect"))
    )
    (net (code "87") (name "unconnected-(J3-Pad5)") (class "Default")
      (node (ref "J3") (pin "5") (pinfunction "5_5") (pintype "passive+no_connect"))
    )
    (net (code "88") (name "unconnected-(J3-Pad6)") (class "Default")
      (node (ref "J3") (pin "6") (pinfunction "6_6") (pintype "passive+no_connect"))
    )
    (net (code "89") (name "unconnected-(J3-Pad7)") (class "Default")
      (node (ref "J3") (pin "7") (pinfunction "7_7") (pintype "passive+no_connect"))
    )
    (net (code "90") (name "unconnected-(J3-Pad8)") (class "Default")
      (node (ref "J3") (pin "8") (pinfunction "8_8") (pintype "passive+no_connect"))
    )
    (net (code "91") (name "unconnected-(J3-Pad9)") (class "Default")
      (node (ref "J3") (pin "9") (pinfunction "9_9") (pintype "passive+no_connect"))
    )
    (net (code "92") (name "unconnected-(J3-Pad10)") (class "Default")
      (node (ref "J3") (pin "10") (pinfunction "10_10") (pintype "passive+no_connect"))
    )
    (net (code "93") (name "unconnected-(J3-Pad11)") (class "Default")
      (node (ref "J3") (pin "11") (pinfunction "11_11") (pintype "passive+no_connect"))
    )
    (net (code "94") (name "unconnected-(J3-Pad12)") (class "Default")
      (node (ref "J3") (pin "12") (pinfunction "12_12") (pintype "passive+no_connect"))
    )
    (net (code "95") (name "unconnected-(J3-Pad13)") (class "Default")
      (node (ref "J3") (pin "13") (pinfunction "13_13") (pintype "passive+no_connect"))
    )
    (net (code "96") (name "unconnected-(J3-Pad15)") (class "Default")
      (node (ref "J3") (pin "15") (pinfunction "15_15") (pintype "passive+no_connect"))
    )
    (net (code "97") (name "unconnected-(J3-Pad17)") (class "Default")
      (node (ref "J3") (pin "17") (pinfunction "17_17") (pintype "passive+no_connect"))
    )
    (net (code "98") (name "unconnected-(J3-Pad18)") (class "Default")
      (node (ref "J3") (pin "18") (pinfunction "18_18") (pintype "passive+no_connect"))
    )
    (net (code "99") (name "unconnected-(J3-Pad19)") (class "Default")
      (node (ref "J3") (pin "19") (pinfunction "19_19") (pintype "passive+no_connect"))
    )
    (net (code "100") (name "unconnected-(J3-Pad20)") (class "Default")
      (node (ref "J3") (pin "20") (pinfunction "20_20") (pintype "passive+no_connect"))
    )
    (net (code "101") (name "unconnected-(J3-Pad21)") (class "Default")
      (node (ref "J3") (pin "21") (pinfunction "21_21") (pintype "passive+no_connect"))
    )
    (net (code "102") (name "unconnected-(J3-Pad22)") (class "Default")
      (node (ref "J3") (pin "22") (pinfunction "22_22") (pintype "passive+no_connect"))
    )
    (net (code "103") (name "unconnected-(J3-Pad23)") (class "Default")
      (node (ref "J3") (pin "23") (pinfunction "23_23") (pintype "passive+no_connect"))
    )
    (net (code "104") (name "unconnected-(J3-Pad24)") (class "Default")
      (node (ref "J3") (pin "24") (pinfunction "24_24") (pintype "passive+no_connect"))
    )
    (net (code "105") (name "unconnected-(J3-Pad25)") (class "Default")
      (node (ref "J3") (pin "25") (pinfunction "25_25") (pintype "passive+no_connect"))
    )
    (net (code "106") (name "unconnected-(J3-Pad26)") (class "Default")
      (node (ref "J3") (pin "26") (pinfunction "26_26") (pintype "passive+no_connect"))
    )
    (net (code "107") (name "unconnected-(J3-Pad27)") (class "Default")
      (node (ref "J3") (pin "27") (pinfunction "27_27") (pintype "passive+no_connect"))
    )
    (net (code "108") (name "unconnected-(J3-Pad28)") (class "Default")
      (node (ref "J3") (pin "28") (pinfunction "28_28") (pintype "passive+no_connect"))
    )
    (net (code "109") (name "unconnected-(J3-Pad29)") (class "Default")
      (node (ref "J3") (pin "29") (pinfunction "29_29") (pintype "passive+no_connect"))
    )
    (net (code "110") (name "unconnected-(J3-Pad30)") (class "Default")
      (node (ref "J3") (pin "30") (pinfunction "30_30") (pintype "passive+no_connect"))
    )
    (net (code "111") (name "unconnected-(J3-Pad31)") (class "Default")
      (node (ref "J3") (pin "31") (pinfunction "31_31") (pintype "passive+no_connect"))
    )
    (net (code "112") (name "unconnected-(J3-Pad32)") (class "Default")
      (node (ref "J3") (pin "32") (pinfunction "32_32") (pintype "passive+no_connect"))
    )
    (net (code "113") (name "unconnected-(J3-Pad33)") (class "Default")
      (node (ref "J3") (pin "33") (pinfunction "33_33") (pintype "passive+no_connect"))
    )
    (net (code "114") (name "unconnected-(J3-Pad34)") (class "Default")
      (node (ref "J3") (pin "34") (pinfunction "34_34") (pintype "passive+no_connect"))
    )
    (net (code "115") (name "unconnected-(J3-RX-Pad16)") (class "Default")
      (node (ref "J3") (pin "16") (pinfunction "RX_16") (pintype "passive"))
    )
    (net (code "116") (name "unconnected-(J3-TX-Pad14)") (class "Default")
      (node (ref "J3") (pin "14") (pinfunction "TX_14") (pintype "passive"))
    )
    (net (code "117") (name "unconnected-(J4-Pad1)") (class "Default")
      (node (ref "J4") (pin "1") (pinfunction "1_1") (pintype "passive+no_connect"))
    )
    (net (code "118") (name "unconnected-(J4-Pad2)") (class "Default")
      (node (ref "J4") (pin "2") (pinfunction "2_2") (pintype "passive+no_connect"))
    )
    (net (code "119") (name "unconnected-(J4-Pad3)") (class "Default")
      (node (ref "J4") (pin "3") (pinfunction "3_3") (pintype "passive+no_connect"))
    )
    (net (code "120") (name "unconnected-(J4-Pad4)") (class "Default")
      (node (ref "J4") (pin "4") (pinfunction "4_4") (pintype "passive+no_connect"))
    )
    (net (code "121") (name "unconnected-(J4-Pad5)") (class "Default")
      (node (ref "J4") (pin "5") (pinfunction "5_5") (pintype "passive+no_connect"))
    )
    (net (code "122") (name "unconnected-(J4-Pad6)") (class "Default")
      (node (ref "J4") (pin "6") (pinfunction "6_6") (pintype "passive+no_connect"))
    )
    (net (code "123") (name "unconnected-(J4-Pad7)") (class "Default")
      (node (ref "J4") (pin "7") (pinfunction "7_7") (pintype "passive+no_connect"))
    )
    (net (code "124") (name "unconnected-(J4-Pad8)") (class "Default")
      (node (ref "J4") (pin "8") (pinfunction "8_8") (pintype "passive+no_connect"))
    )
    (net (code "125") (name "unconnected-(J4-Pad9)") (class "Default")
      (node (ref "J4") (pin "9") (pinfunction "9_9") (pintype "passive+no_connect"))
    )
    (net (code "126") (name "unconnected-(J4-Pad11)") (class "Default")
      (node (ref "J4") (pin "11") (pinfunction "11_11") (pintype "passive+no_connect"))
    )
    (net (code "127") (name "unconnected-(J4-Pad13)") (class "Default")
      (node (ref "J4") (pin "13") (pinfunction "13_13") (pintype "passive+no_connect"))
    )
    (net (code "128") (name "unconnected-(J4-Pad15)") (class "Default")
      (node (ref "J4") (pin "15") (pinfunction "15_15") (pintype "passive+no_connect"))
    )
    (net (code "129") (name "unconnected-(J4-Pad16)") (class "Default")
      (node (ref "J4") (pin "16") (pinfunction "16_16") (pintype "passive+no_connect"))
    )
    (net (code "130") (name "unconnected-(J4-Pad17)") (class "Default")
      (node (ref "J4") (pin "17") (pinfunction "17_17") (pintype "passive+no_connect"))
    )
    (net (code "131") (name "unconnected-(J4-Pad18)") (class "Default")
      (node (ref "J4") (pin "18") (pinfunction "18_18") (pintype "passive+no_connect"))
    )
    (net (code "132") (name "unconnected-(J4-Pad19)") (class "Default")
      (node (ref "J4") (pin "19") (pinfunction "19_19") (pintype "passive+no_connect"))
    )
    (net (code "133") (name "unconnected-(J4-Pad20)") (class "Default")
      (node (ref "J4") (pin "20") (pinfunction "20_20") (pintype "passive+no_connect"))
    )
    (net (code "134") (name "unconnected-(U2-CLKO{slash}SOF-Pad3)") (class "Default")
      (node (ref "U2") (pin "3") (pinfunction "CLKO/SOF_3") (pintype "output+no_connect"))
    )
    (net (code "135") (name "unconnected-(U2-OSC2-Pad5)") (class "Default")
      (node (ref "U2") (pin "5") (pinfunction "OSC2_5") (pintype "output+no_connect"))
    )
    (net (code "136") (name "unconnected-(U2-~{INT0}{slash}GPIO0{slash}XSTBY-Pad9)") (class "Default")
      (node (ref "U2") (pin "9") (pinfunction "~{INT0}/GPIO0/XSTBY_9") (pintype "bidirectional+no_connect"))
    )
    (net (code "137") (name "unconnected-(U2-~{INT1}{slash}GPIO1-Pad8)") (class "Default")
      (node (ref "U2") (pin "8") (pinfunction "~{INT1}/GPIO1_8") (pintype "bidirectional+no_connect"))
    )
    (net (code "138") (name "unconnected-(U2-~{INT}-Pad4)") (class "Default")
      (node (ref "U2") (pin "4") (pinfunction "~{INT}_4") (pintype "output+no_connect"))
    )
    (net (code "139") (name "unconnected-(U3-GND-PadEPAD)") (class "Default")
      (node (ref "U3") (pin "EPAD") (pinfunction "GND_EPAD") (pintype "power_in"))
    )
  )
)
